# picoDotstar.net
KiCad netlist of a schematic drawn in EAGLE
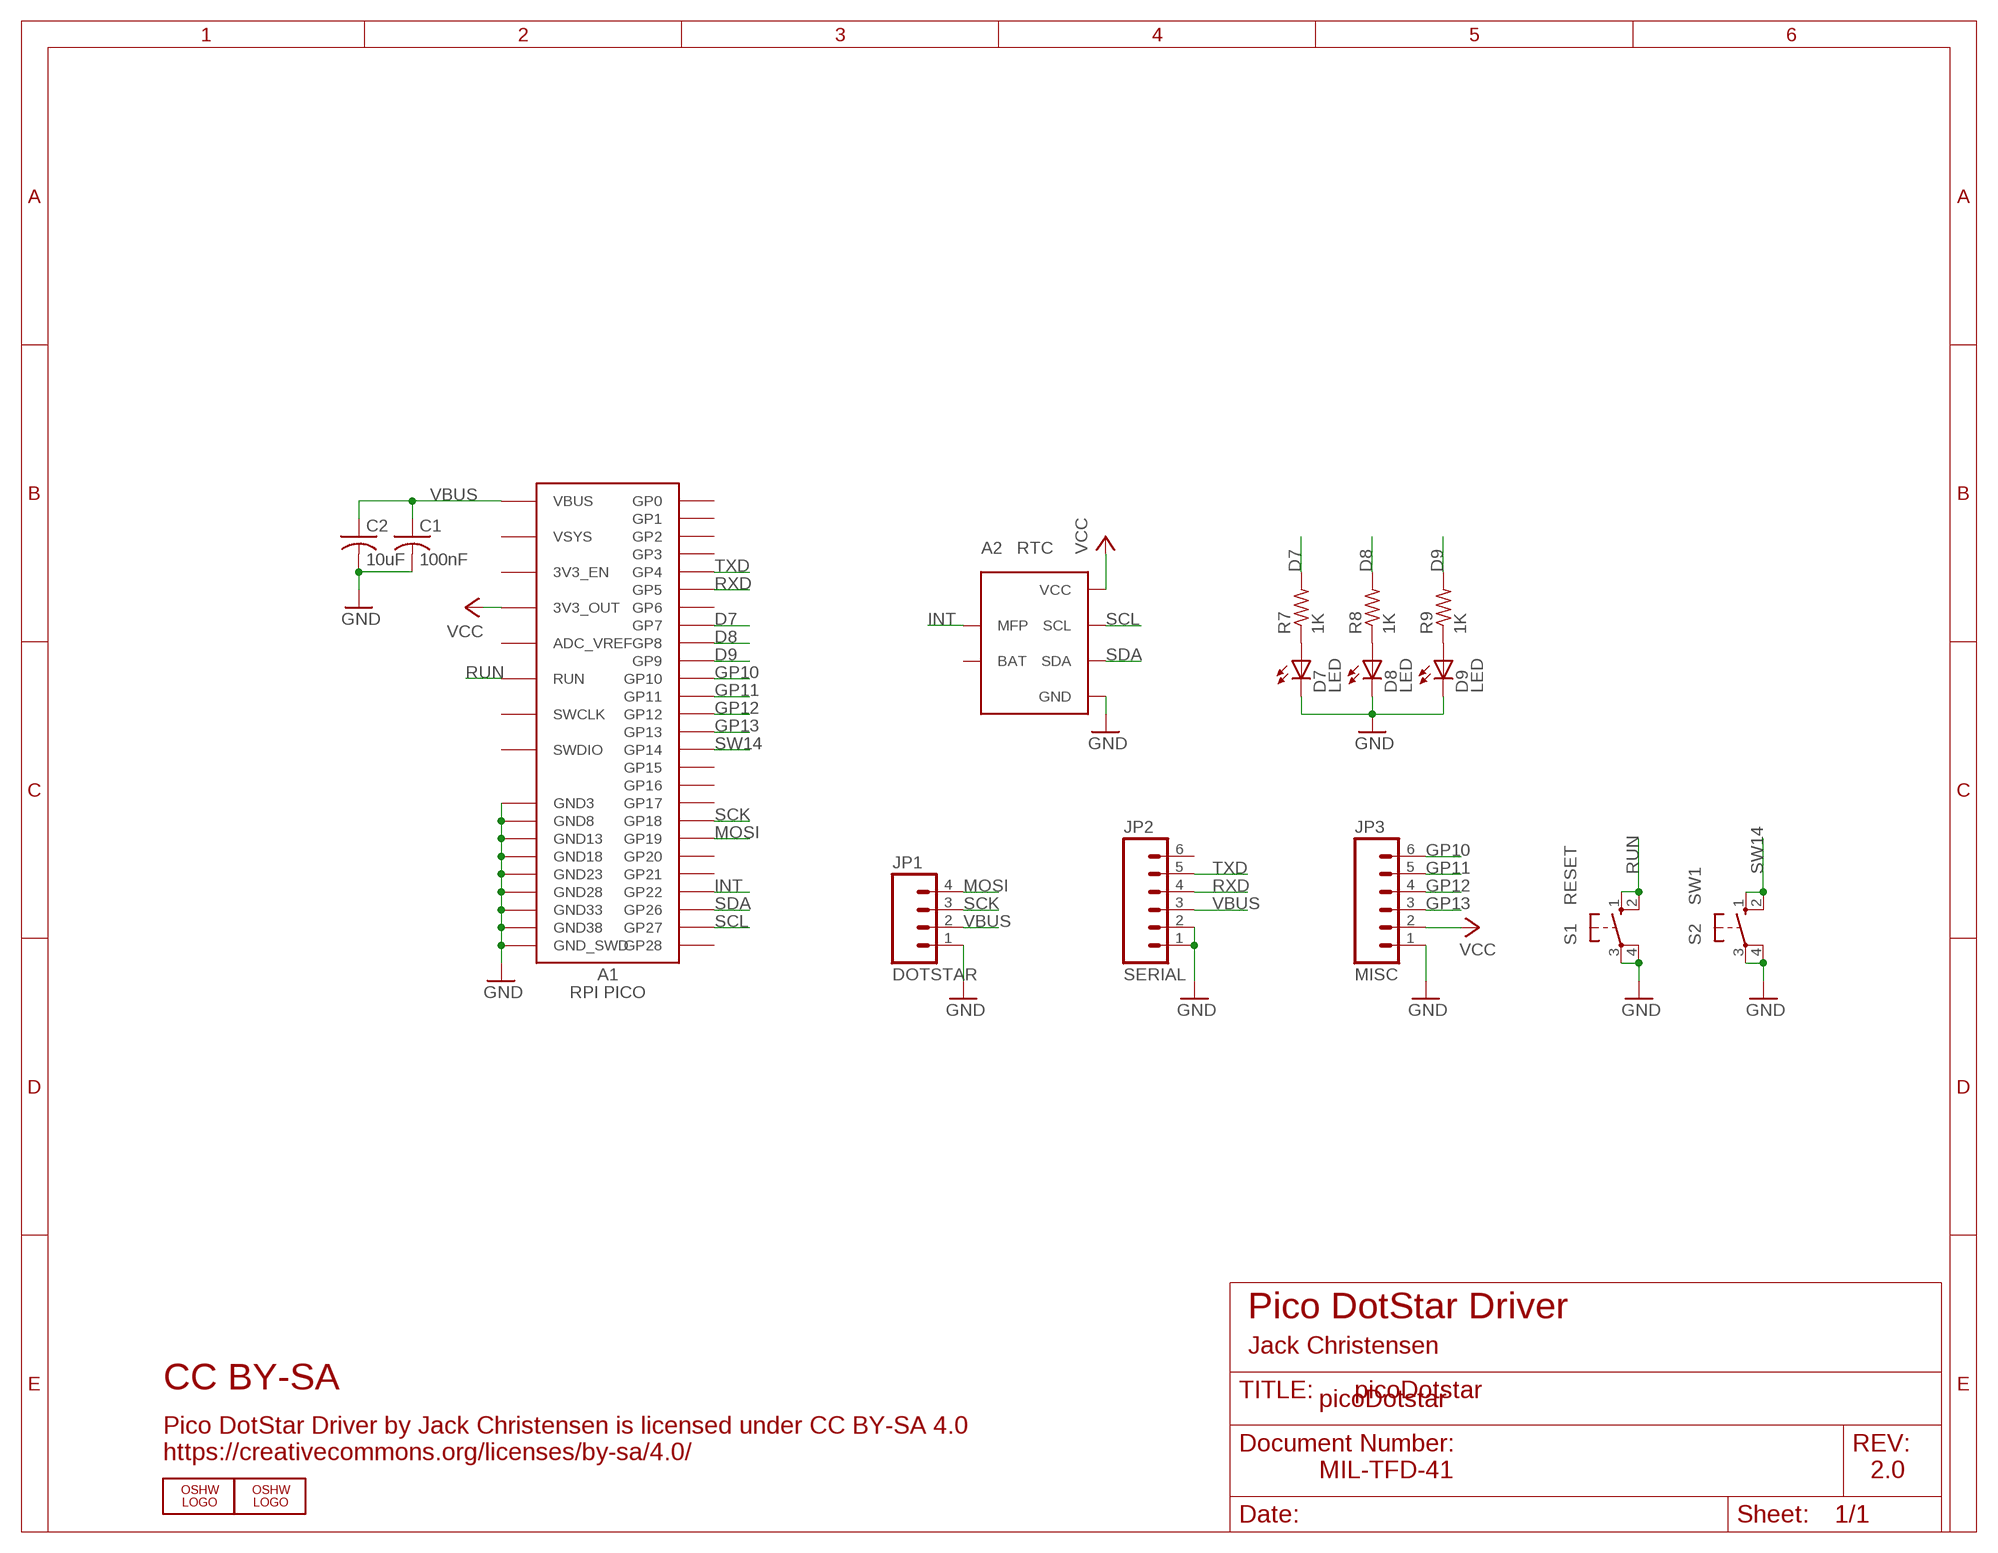
[diagram p0: schematic, sheet 1]

(export (version "E")
  (design (tool "Eeschema 10.0.6"))
  (components
    (comp (ref "A1")
      (value "RPI PICO")
      (footprint "eagle-import:PICO")
      (libsource (lib "eagle-import") (part "PICOPICO"))
    )
    (comp (ref "A2")
      (value "RTC")
      (footprint "eagle-import:RTC79412")
      (libsource (lib "eagle-import") (part "RTC79412"))
    )
    (comp (ref "C1")
      (value "100nF")
      (footprint "eagle-import:M0805")
      (libsource (lib "eagle-import") (part "C-USM0805"))
    )
    (comp (ref "C2")
      (value "10uF")
      (footprint "eagle-import:M0805")
      (libsource (lib "eagle-import") (part "C-USM0805"))
    )
    (comp (ref "D7")
      (value "LED")
      (footprint "eagle-import:D0805")
      (libsource (lib "eagle-import") (part "LEDD0805"))
    )
    (comp (ref "D8")
      (value "LED")
      (footprint "eagle-import:D0805")
      (libsource (lib "eagle-import") (part "LEDD0805"))
    )
    (comp (ref "D9")
      (value "LED")
      (footprint "eagle-import:D0805")
      (libsource (lib "eagle-import") (part "LEDD0805"))
    )
    (comp (ref "JP1")
      (value "DOTSTAR")
      (footprint "eagle-import:1X04_LOCK")
      (libsource (lib "eagle-import") (part "M04LOCK"))
    )
    (comp (ref "JP2")
      (value "SERIAL")
      (footprint "eagle-import:1X06_LOCK")
      (libsource (lib "eagle-import") (part "M06LOCK"))
    )
    (comp (ref "JP3")
      (value "MISC")
      (footprint "eagle-import:1X06_LOCK")
      (libsource (lib "eagle-import") (part "M06LOCK"))
    )
    (comp (ref "LOGO2")
      (value "OSHW_LOGO_8MILX0100-NT")
      (footprint "eagle-import:OSHW_8X100_NOTEXT")
      (libsource (lib "eagle-import") (part "OSHW_LOGO_8MILX0100-NT"))
    )
    (comp (ref "LOGO3")
      (value "OSHW_LOGO_8MILX0150-NT")
      (footprint "eagle-import:OSHW_8X150_NOTEXT")
      (libsource (lib "eagle-import") (part "OSHW_LOGO_8MILX0150-NT"))
    )
    (comp (ref "R7")
      (value "1K")
      (footprint "eagle-import:M0805")
      (libsource (lib "eagle-import") (part "R-US_M0805"))
    )
    (comp (ref "R8")
      (value "1K")
      (footprint "eagle-import:M0805")
      (libsource (lib "eagle-import") (part "R-US_M0805"))
    )
    (comp (ref "R9")
      (value "1K")
      (footprint "eagle-import:M0805")
      (libsource (lib "eagle-import") (part "R-US_M0805"))
    )
    (comp (ref "S1")
      (value "RESET")
      (footprint "eagle-import:B3F-10XXOCT")
      (libsource (lib "eagle-import") (part "10-XXOCT"))
    )
    (comp (ref "S2")
      (value "SW1")
      (footprint "eagle-import:B3F-10XXOCT")
      (libsource (lib "eagle-import") (part "10-XXOCT"))
    )
  )
  (nets
    (net (code "1") (name "/D7") (class "Default")
      (node (ref "A1") (pin "P$10") (pinfunction "GP7_P$10") (pintype "bidirectional"))
      (node (ref "R7") (pin "2") (pinfunction "2_2") (pintype "passive"))
    )
    (net (code "2") (name "/D8") (class "Default")
      (node (ref "A1") (pin "P$11") (pinfunction "GP8_P$11") (pintype "bidirectional"))
      (node (ref "R8") (pin "2") (pinfunction "2_2") (pintype "passive"))
    )
    (net (code "3") (name "/D9") (class "Default")
      (node (ref "A1") (pin "P$12") (pinfunction "GP9_P$12") (pintype "bidirectional"))
      (node (ref "R9") (pin "2") (pinfunction "2_2") (pintype "passive"))
    )
    (net (code "4") (name "/GP10") (class "Default")
      (node (ref "A1") (pin "P$14") (pinfunction "GP10_P$14") (pintype "bidirectional"))
      (node (ref "JP3") (pin "6") (pinfunction "6_6") (pintype "passive"))
    )
    (net (code "5") (name "/GP11") (class "Default")
      (node (ref "A1") (pin "P$15") (pinfunction "GP11_P$15") (pintype "bidirectional"))
      (node (ref "JP3") (pin "5") (pinfunction "5_5") (pintype "passive"))
    )
    (net (code "6") (name "/GP12") (class "Default")
      (node (ref "A1") (pin "P$16") (pinfunction "GP12_P$16") (pintype "bidirectional"))
      (node (ref "JP3") (pin "4") (pinfunction "4_4") (pintype "passive"))
    )
    (net (code "7") (name "/GP13") (class "Default")
      (node (ref "A1") (pin "P$17") (pinfunction "GP13_P$17") (pintype "bidirectional"))
      (node (ref "JP3") (pin "3") (pinfunction "3_3") (pintype "passive"))
    )
    (net (code "8") (name "/INT") (class "Default")
      (node (ref "A1") (pin "P$29") (pinfunction "GP22_P$29") (pintype "bidirectional"))
      (node (ref "A2") (pin "3") (pinfunction "MFP_3") (pintype "passive"))
    )
    (net (code "9") (name "/MOSI") (class "Default")
      (node (ref "A1") (pin "P$25") (pinfunction "GP19_P$25") (pintype "bidirectional"))
      (node (ref "JP1") (pin "4") (pinfunction "4_4") (pintype "passive"))
    )
    (net (code "10") (name "/RUN") (class "Default")
      (node (ref "A1") (pin "P$30") (pinfunction "RUN_P$30") (pintype "bidirectional"))
      (node (ref "S1") (pin "1") (pinfunction "S_1") (pintype "passive"))
      (node (ref "S1") (pin "2") (pinfunction "S1_2") (pintype "passive"))
    )
    (net (code "11") (name "/RXD") (class "Default")
      (node (ref "A1") (pin "P$07") (pinfunction "GP5_P$07") (pintype "bidirectional"))
      (node (ref "JP2") (pin "4") (pinfunction "4_4") (pintype "passive"))
    )
    (net (code "12") (name "/SCK") (class "Default")
      (node (ref "A1") (pin "P$24") (pinfunction "GP18_P$24") (pintype "bidirectional"))
      (node (ref "JP1") (pin "3") (pinfunction "3_3") (pintype "passive"))
    )
    (net (code "13") (name "/SCL") (class "Default")
      (node (ref "A1") (pin "P$32") (pinfunction "GP27_P$32") (pintype "bidirectional"))
      (node (ref "A2") (pin "6") (pinfunction "SCL_6") (pintype "passive"))
    )
    (net (code "14") (name "/SDA") (class "Default")
      (node (ref "A1") (pin "P$31") (pinfunction "GP26_P$31") (pintype "bidirectional"))
      (node (ref "A2") (pin "5") (pinfunction "SDA_5") (pintype "passive"))
    )
    (net (code "15") (name "/SW14") (class "Default")
      (node (ref "A1") (pin "P$19") (pinfunction "GP14_P$19") (pintype "bidirectional"))
      (node (ref "S2") (pin "1") (pinfunction "S_1") (pintype "passive"))
      (node (ref "S2") (pin "2") (pinfunction "S1_2") (pintype "passive"))
    )
    (net (code "16") (name "/TXD") (class "Default")
      (node (ref "A1") (pin "P$06") (pinfunction "GP4_P$06") (pintype "bidirectional"))
      (node (ref "JP2") (pin "5") (pinfunction "5_5") (pintype "passive"))
    )
    (net (code "17") (name "/VBUS") (class "Default")
      (node (ref "A1") (pin "P$40") (pinfunction "VBUS_P$40") (pintype "bidirectional"))
      (node (ref "C1") (pin "1") (pinfunction "1_1") (pintype "passive"))
      (node (ref "C2") (pin "1") (pinfunction "1_1") (pintype "passive"))
      (node (ref "JP1") (pin "2") (pinfunction "2_2") (pintype "passive"))
      (node (ref "JP2") (pin "3") (pinfunction "3_3") (pintype "passive"))
    )
    (net (code "18") (name "GND") (class "Default")
      (node (ref "A1") (pin "P$03") (pinfunction "GND3_P$03") (pintype "bidirectional"))
      (node (ref "A1") (pin "P$08") (pinfunction "GND8_P$08") (pintype "bidirectional"))
      (node (ref "A1") (pin "P$13") (pinfunction "GND13_P$13") (pintype "bidirectional"))
      (node (ref "A1") (pin "P$18") (pinfunction "GND18_P$18") (pintype "bidirectional"))
      (node (ref "A1") (pin "P$23") (pinfunction "GND23_P$23") (pintype "bidirectional"))
      (node (ref "A1") (pin "P$28") (pinfunction "GND28_P$28") (pintype "bidirectional"))
      (node (ref "A1") (pin "P$33") (pinfunction "GND33_P$33") (pintype "bidirectional"))
      (node (ref "A1") (pin "P$38") (pinfunction "GND38_P$38") (pintype "bidirectional"))
      (node (ref "A1") (pin "P$SWGND") (pinfunction "GND_SWD_P$SWGND") (pintype "bidirectional"))
      (node (ref "A2") (pin "8") (pinfunction "GND_8") (pintype "passive"))
      (node (ref "C1") (pin "2") (pinfunction "2_2") (pintype "passive"))
      (node (ref "C2") (pin "2") (pinfunction "2_2") (pintype "passive"))
      (node (ref "D7") (pin "K") (pinfunction "C_K") (pintype "passive"))
      (node (ref "D8") (pin "K") (pinfunction "C_K") (pintype "passive"))
      (node (ref "D9") (pin "K") (pinfunction "C_K") (pintype "passive"))
      (node (ref "JP1") (pin "1") (pinfunction "1_1") (pintype "passive"))
      (node (ref "JP2") (pin "1") (pinfunction "1_1") (pintype "passive"))
      (node (ref "JP2") (pin "2") (pinfunction "2_2") (pintype "passive"))
      (node (ref "JP3") (pin "1") (pinfunction "1_1") (pintype "passive"))
      (node (ref "S1") (pin "3") (pinfunction "P_3") (pintype "passive"))
      (node (ref "S1") (pin "4") (pinfunction "P1_4") (pintype "passive"))
      (node (ref "S2") (pin "3") (pinfunction "P_3") (pintype "passive"))
      (node (ref "S2") (pin "4") (pinfunction "P1_4") (pintype "passive"))
    )
    (net (code "19") (name "Net-(D7-PadA)") (class "Default")
      (node (ref "D7") (pin "A") (pinfunction "A_A") (pintype "passive"))
      (node (ref "R7") (pin "1") (pinfunction "1_1") (pintype "passive"))
    )
    (net (code "20") (name "Net-(D8-PadA)") (class "Default")
      (node (ref "D8") (pin "A") (pinfunction "A_A") (pintype "passive"))
      (node (ref "R8") (pin "1") (pinfunction "1_1") (pintype "passive"))
    )
    (net (code "21") (name "Net-(D9-PadA)") (class "Default")
      (node (ref "D9") (pin "A") (pinfunction "A_A") (pintype "passive"))
      (node (ref "R9") (pin "1") (pinfunction "1_1") (pintype "passive"))
    )
    (net (code "22") (name "VCC") (class "Default")
      (node (ref "A1") (pin "P$36") (pinfunction "3V3_OUT_P$36") (pintype "bidirectional"))
      (node (ref "A2") (pin "7") (pinfunction "VCC_7") (pintype "passive"))
      (node (ref "JP3") (pin "2") (pinfunction "2_2") (pintype "passive"))
    )
    (net (code "23") (name "unconnected-(A1-3V3_EN-PadP$37)") (class "Default")
      (node (ref "A1") (pin "P$37") (pinfunction "3V3_EN_P$37") (pintype "bidirectional"))
    )
    (net (code "24") (name "unconnected-(A1-ADC_VREF-PadP$35)") (class "Default")
      (node (ref "A1") (pin "P$35") (pinfunction "ADC_VREF_P$35") (pintype "bidirectional"))
    )
    (net (code "25") (name "unconnected-(A1-GP0-PadP$01)") (class "Default")
      (node (ref "A1") (pin "P$01") (pinfunction "GP0_P$01") (pintype "bidirectional"))
    )
    (net (code "26") (name "unconnected-(A1-GP1-PadP$02)") (class "Default")
      (node (ref "A1") (pin "P$02") (pinfunction "GP1_P$02") (pintype "bidirectional"))
    )
    (net (code "27") (name "unconnected-(A1-GP2-PadP$04)") (class "Default")
      (node (ref "A1") (pin "P$04") (pinfunction "GP2_P$04") (pintype "bidirectional"))
    )
    (net (code "28") (name "unconnected-(A1-GP3-PadP$05)") (class "Default")
      (node (ref "A1") (pin "P$05") (pinfunction "GP3_P$05") (pintype "bidirectional"))
    )
    (net (code "29") (name "unconnected-(A1-GP6-PadP$09)") (class "Default")
      (node (ref "A1") (pin "P$09") (pinfunction "GP6_P$09") (pintype "bidirectional"))
    )
    (net (code "30") (name "unconnected-(A1-GP15-PadP$20)") (class "Default")
      (node (ref "A1") (pin "P$20") (pinfunction "GP15_P$20") (pintype "bidirectional"))
    )
    (net (code "31") (name "unconnected-(A1-GP16-PadP$21)") (class "Default")
      (node (ref "A1") (pin "P$21") (pinfunction "GP16_P$21") (pintype "bidirectional"))
    )
    (net (code "32") (name "unconnected-(A1-GP17-PadP$22)") (class "Default")
      (node (ref "A1") (pin "P$22") (pinfunction "GP17_P$22") (pintype "bidirectional"))
    )
    (net (code "33") (name "unconnected-(A1-GP20-PadP$26)") (class "Default")
      (node (ref "A1") (pin "P$26") (pinfunction "GP20_P$26") (pintype "bidirectional"))
    )
    (net (code "34") (name "unconnected-(A1-GP21-PadP$27)") (class "Default")
      (node (ref "A1") (pin "P$27") (pinfunction "GP21_P$27") (pintype "bidirectional"))
    )
    (net (code "35") (name "unconnected-(A1-GP28-PadP$34)") (class "Default")
      (node (ref "A1") (pin "P$34") (pinfunction "GP28_P$34") (pintype "bidirectional"))
    )
    (net (code "36") (name "unconnected-(A1-SWCLK-PadP$SWCLK)") (class "Default")
      (node (ref "A1") (pin "P$SWCLK") (pinfunction "SWCLK_P$SWCLK") (pintype "bidirectional"))
    )
    (net (code "37") (name "unconnected-(A1-SWDIO-PadP$SWDIO)") (class "Default")
      (node (ref "A1") (pin "P$SWDIO") (pinfunction "SWDIO_P$SWDIO") (pintype "bidirectional"))
    )
    (net (code "38") (name "unconnected-(A1-VSYS-PadP$39)") (class "Default")
      (node (ref "A1") (pin "P$39") (pinfunction "VSYS_P$39") (pintype "bidirectional"))
    )
    (net (code "39") (name "unconnected-(A2-BAT-Pad1)") (class "Default")
      (node (ref "A2") (pin "1") (pinfunction "BAT_1") (pintype "passive"))
    )
    (net (code "40") (name "unconnected-(JP2-Pad6)") (class "Default")
      (node (ref "JP2") (pin "6") (pinfunction "6_6") (pintype "passive"))
    )
  )
)
